# layout3.net
KiCad netlist of a schematic drawn in EAGLE
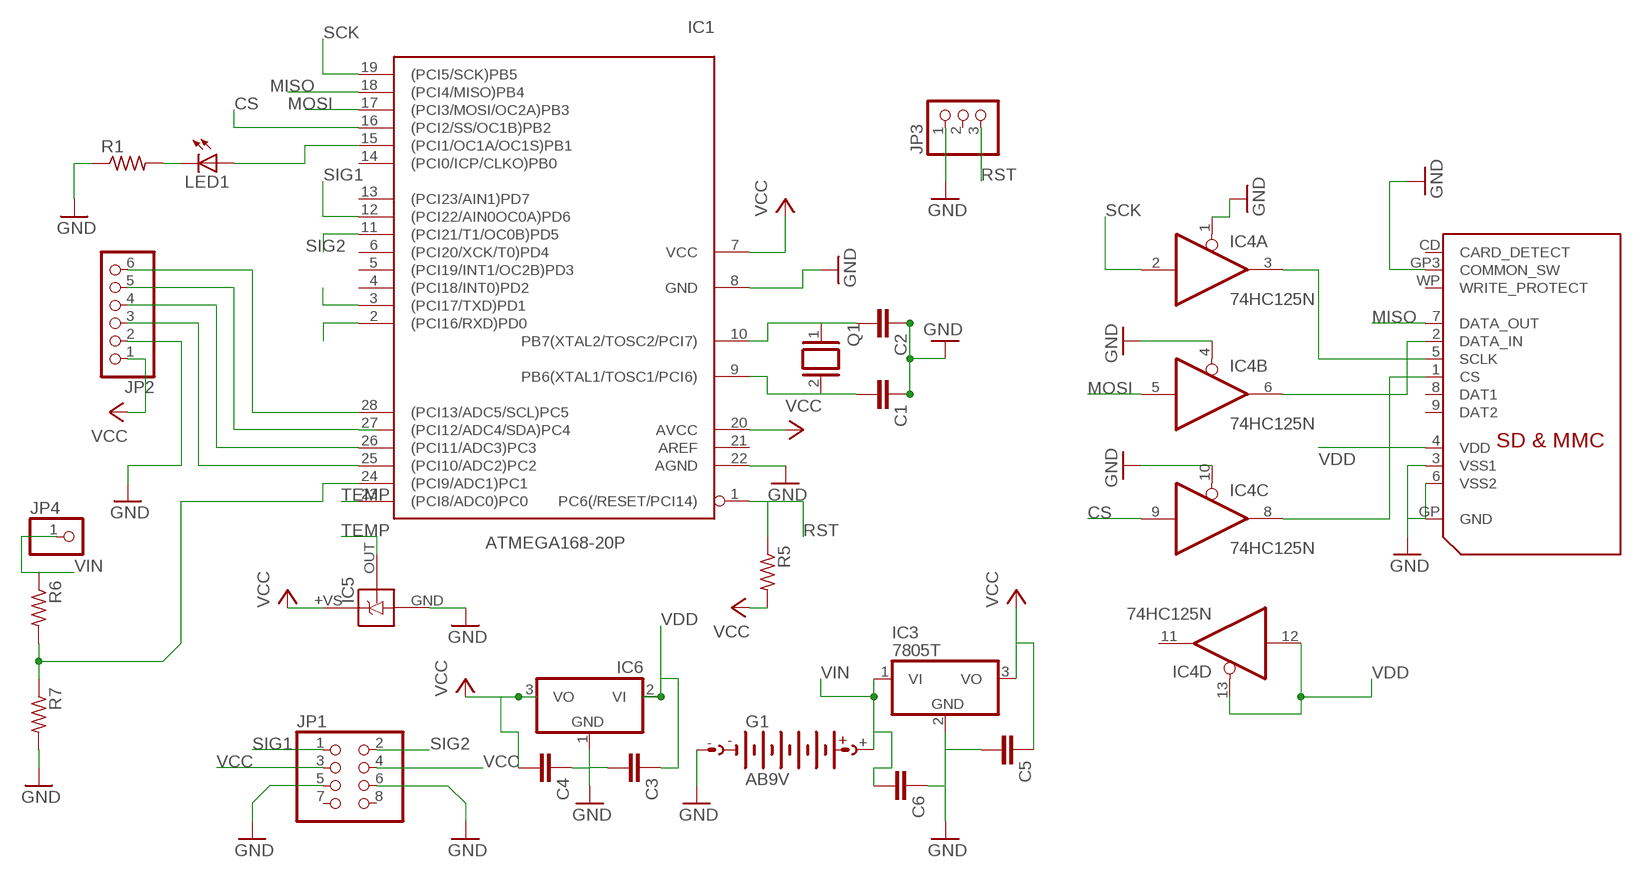
[diagram p0: schematic, sheet 1]

(export (version "E")
  (design (tool "Eeschema 10.0.6"))
  (components
    (comp (ref "C1")
      (value "C-EU025-025X050")
      (footprint "eagle-import:C025-025X050")
      (libsource (lib "eagle-import") (part "C-EU025-025X050"))
    )
    (comp (ref "C2")
      (value "C-EU025-025X050")
      (footprint "eagle-import:C025-025X050")
      (libsource (lib "eagle-import") (part "C-EU025-025X050"))
    )
    (comp (ref "C3")
      (value "C-EU025-025X050")
      (footprint "eagle-import:C025-025X050")
      (libsource (lib "eagle-import") (part "C-EU025-025X050"))
    )
    (comp (ref "C4")
      (value "C-EU025-025X050")
      (footprint "eagle-import:C025-025X050")
      (libsource (lib "eagle-import") (part "C-EU025-025X050"))
    )
    (comp (ref "C5")
      (value "C-EU025-025X050")
      (footprint "eagle-import:C025-025X050")
      (libsource (lib "eagle-import") (part "C-EU025-025X050"))
    )
    (comp (ref "C6")
      (value "C-EU025-025X050")
      (footprint "eagle-import:C025-025X050")
      (libsource (lib "eagle-import") (part "C-EU025-025X050"))
    )
    (comp (ref "G1")
      (value "AB9V")
      (footprint "eagle-import:AB9V")
      (libsource (lib "eagle-import") (part "AB9V"))
    )
    (comp (ref "IC1")
      (value "ATMEGA168-20P")
      (footprint "eagle-import:DIL28-3")
      (libsource (lib "eagle-import") (part "ATMEGA168P-20"))
    )
    (comp (ref "IC3")
      (value "7805T")
      (footprint "eagle-import:TO220H")
      (libsource (lib "eagle-import") (part "78T05"))
    )
    (comp (ref "IC4")
      (value "74HC125N")
      (footprint "eagle-import:DIL14")
      (libsource (lib "eagle-import") (part "74125NHC"))
    )
    (comp (ref "IC5")
      (value "LM35")
      (footprint "eagle-import:TO-92-")
      (libsource (lib "eagle-import") (part "LM35"))
    )
    (comp (ref "IC6")
      (value "7906T")
      (footprint "eagle-import:TO220H")
      (libsource (lib "eagle-import") (part "79T06"))
    )
    (comp (ref "JP1")
      (value "PINHD-2X4")
      (footprint "eagle-import:2X04")
      (libsource (lib "eagle-import") (part "PINHD-2X4"))
    )
    (comp (ref "JP2")
      (value "PINHD-1X6CB")
      (footprint "eagle-import:1X06-CLEANBIG")
      (libsource (lib "eagle-import") (part "PINHD-1X6CB"))
    )
    (comp (ref "JP3")
      (value "PINHD-1X3CB")
      (footprint "eagle-import:1X03-CLEANBIG")
      (libsource (lib "eagle-import") (part "PINHD-1X3CB"))
    )
    (comp (ref "JP4")
      (value "PINHD-1X1CB")
      (footprint "eagle-import:1X01-CLEANBIG")
      (libsource (lib "eagle-import") (part "PINHD-1X1CB"))
    )
    (comp (ref "LED1")
      (value "LED5MM")
      (footprint "eagle-import:LED5MM")
      (libsource (lib "eagle-import") (part "LED5MM"))
    )
    (comp (ref "Q1")
      (value "XTAL/S")
      (footprint "eagle-import:QS")
      (libsource (lib "eagle-import") (part "XTAL/S"))
    )
    (comp (ref "R1")
      (value "R-US_0207/10")
      (footprint "eagle-import:0207_10")
      (libsource (lib "eagle-import") (part "R-US_0207/10"))
    )
    (comp (ref "R5")
      (value "R-US_0207/10")
      (footprint "eagle-import:0207_10")
      (libsource (lib "eagle-import") (part "R-US_0207/10"))
    )
    (comp (ref "R6")
      (value "R-US_0207/10")
      (footprint "eagle-import:0207_10")
      (libsource (lib "eagle-import") (part "R-US_0207/10"))
    )
    (comp (ref "R7")
      (value "R-US_0207/10")
      (footprint "eagle-import:0207_10")
      (libsource (lib "eagle-import") (part "R-US_0207/10"))
    )
    (comp (ref "U$1")
      (value "SDMMC06132")
      (footprint "eagle-import:06132")
      (libsource (lib "eagle-import") (part "SDMMC06132"))
    )
  )
  (nets
    (net (code "1") (name "/CS") (class "Default")
      (node (ref "IC1") (pin "16") (pinfunction "(PCI2/SS/OC1B)PB2_16") (pintype "bidirectional"))
      (node (ref "IC4") (pin "9") (pinfunction "I_9") (pintype "input"))
    )
    (net (code "2") (name "/MISO") (class "Default")
      (node (ref "IC1") (pin "18") (pinfunction "(PCI4/MISO)PB4_18") (pintype "bidirectional"))
      (node (ref "U$1") (pin "7") (pinfunction "DATA_OUT_7") (pintype "output"))
    )
    (net (code "3") (name "/MOSI") (class "Default")
      (node (ref "IC1") (pin "17") (pinfunction "(PCI3/MOSI/OC2A)PB3_17") (pintype "bidirectional"))
      (node (ref "IC4") (pin "5") (pinfunction "I_5") (pintype "input"))
    )
    (net (code "4") (name "/RST") (class "Default")
      (node (ref "IC1") (pin "1") (pinfunction "PC6(/RESET/PCI14)_1") (pintype "bidirectional"))
      (node (ref "JP3") (pin "3") (pinfunction "3_3") (pintype "passive"))
      (node (ref "R5") (pin "1") (pinfunction "1_1") (pintype "passive"))
    )
    (net (code "5") (name "/SCK") (class "Default")
      (node (ref "IC1") (pin "19") (pinfunction "(PCI5/SCK)PB5_19") (pintype "bidirectional"))
      (node (ref "IC4") (pin "2") (pinfunction "I_2") (pintype "input"))
    )
    (net (code "6") (name "/SIG1") (class "Default")
      (node (ref "IC1") (pin "12") (pinfunction "(PCI22/AIN0OC0A)PD6_12") (pintype "bidirectional"))
      (node (ref "JP1") (pin "1") (pinfunction "1_1") (pintype "passive"))
    )
    (net (code "7") (name "/SIG2") (class "Default")
      (node (ref "IC1") (pin "11") (pinfunction "(PCI21/T1/OC0B)PD5_11") (pintype "bidirectional"))
      (node (ref "JP1") (pin "2") (pinfunction "2_2") (pintype "passive"))
    )
    (net (code "8") (name "/TEMP") (class "Default")
      (node (ref "IC1") (pin "23") (pinfunction "(PCI8/ADC0)PC0_23") (pintype "bidirectional"))
      (node (ref "IC5") (pin "OUT") (pinfunction "OUT_OUT") (pintype "bidirectional"))
    )
    (net (code "9") (name "/VDD") (class "Default")
      (node (ref "C3") (pin "1") (pinfunction "1_1") (pintype "passive"))
      (node (ref "IC4") (pin "12") (pinfunction "I_12") (pintype "input"))
      (node (ref "IC4") (pin "13") (pinfunction "OE_13") (pintype "input"))
      (node (ref "IC6") (pin "2") (pinfunction "VI_2") (pintype "input"))
      (node (ref "U$1") (pin "4") (pinfunction "VDD_4") (pintype "power_in"))
    )
    (net (code "10") (name "/VIN") (class "Default")
      (node (ref "C6") (pin "2") (pinfunction "2_2") (pintype "passive"))
      (node (ref "G1") (pin "+") (pinfunction "+_+") (pintype "passive"))
      (node (ref "IC3") (pin "1") (pinfunction "VI_1") (pintype "input"))
      (node (ref "JP4") (pin "1") (pinfunction "1_1") (pintype "passive"))
      (node (ref "R6") (pin "1") (pinfunction "1_1") (pintype "passive"))
    )
    (net (code "11") (name "GND") (class "Default")
      (node (ref "C1") (pin "1") (pinfunction "1_1") (pintype "passive"))
      (node (ref "C2") (pin "1") (pinfunction "1_1") (pintype "passive"))
      (node (ref "C3") (pin "2") (pinfunction "2_2") (pintype "passive"))
      (node (ref "C4") (pin "1") (pinfunction "1_1") (pintype "passive"))
      (node (ref "C5") (pin "2") (pinfunction "2_2") (pintype "passive"))
      (node (ref "C6") (pin "1") (pinfunction "1_1") (pintype "passive"))
      (node (ref "G1") (pin "-") (pinfunction "-_-") (pintype "passive"))
      (node (ref "IC1") (pin "22") (pinfunction "AGND_22") (pintype "bidirectional"))
      (node (ref "IC1") (pin "8") (pinfunction "GND_8") (pintype "bidirectional"))
      (node (ref "IC3") (pin "2") (pinfunction "GND_2") (pintype "passive"))
      (node (ref "IC4") (pin "1") (pinfunction "OE_1") (pintype "input"))
      (node (ref "IC4") (pin "10") (pinfunction "OE_10") (pintype "input"))
      (node (ref "IC4") (pin "4") (pinfunction "OE_4") (pintype "input"))
      (node (ref "IC5") (pin "GND") (pinfunction "GND_GND") (pintype "bidirectional"))
      (node (ref "IC6") (pin "1") (pinfunction "GND_1") (pintype "passive"))
      (node (ref "JP1") (pin "5") (pinfunction "5_5") (pintype "passive"))
      (node (ref "JP1") (pin "6") (pinfunction "6_6") (pintype "passive"))
      (node (ref "JP2") (pin "2") (pinfunction "2_2") (pintype "passive"))
      (node (ref "JP3") (pin "1") (pinfunction "1_1") (pintype "passive"))
      (node (ref "R1") (pin "1") (pinfunction "1_1") (pintype "passive"))
      (node (ref "R7") (pin "2") (pinfunction "2_2") (pintype "passive"))
      (node (ref "U$1") (pin "3") (pinfunction "VSS1_3") (pintype "power_in"))
      (node (ref "U$1") (pin "6") (pinfunction "VSS2_6") (pintype "power_in"))
      (node (ref "U$1") (pin "GP") (pinfunction "GND_GP") (pintype "power_in"))
      (node (ref "U$1") (pin "GP3") (pinfunction "COMMON_SW_GP3") (pintype "passive"))
    )
    (net (code "12") (name "Net-(IC1-(PCI1{slash}OC1A{slash}OC1S)PB1)") (class "Default")
      (node (ref "IC1") (pin "15") (pinfunction "(PCI1/OC1A/OC1S)PB1_15") (pintype "bidirectional"))
      (node (ref "LED1") (pin "A") (pinfunction "A_A") (pintype "passive"))
    )
    (net (code "13") (name "Net-(IC1-(PCI9{slash}ADC1)PC1)") (class "Default")
      (node (ref "IC1") (pin "24") (pinfunction "(PCI9/ADC1)PC1_24") (pintype "bidirectional"))
      (node (ref "R6") (pin "2") (pinfunction "2_2") (pintype "passive"))
      (node (ref "R7") (pin "1") (pinfunction "1_1") (pintype "passive"))
    )
    (net (code "14") (name "Net-(IC1-(PCI10{slash}ADC2)PC2)") (class "Default")
      (node (ref "IC1") (pin "25") (pinfunction "(PCI10/ADC2)PC2_25") (pintype "bidirectional"))
      (node (ref "JP2") (pin "3") (pinfunction "3_3") (pintype "passive"))
    )
    (net (code "15") (name "Net-(IC1-(PCI11{slash}ADC3)PC3)") (class "Default")
      (node (ref "IC1") (pin "26") (pinfunction "(PCI11/ADC3)PC3_26") (pintype "bidirectional"))
      (node (ref "JP2") (pin "4") (pinfunction "4_4") (pintype "passive"))
    )
    (net (code "16") (name "Net-(IC1-(PCI12{slash}ADC4{slash}SDA)PC4)") (class "Default")
      (node (ref "IC1") (pin "27") (pinfunction "(PCI12/ADC4/SDA)PC4_27") (pintype "bidirectional"))
      (node (ref "JP2") (pin "5") (pinfunction "5_5") (pintype "passive"))
    )
    (net (code "17") (name "Net-(IC1-(PCI13{slash}ADC5{slash}SCL)PC5)") (class "Default")
      (node (ref "IC1") (pin "28") (pinfunction "(PCI13/ADC5/SCL)PC5_28") (pintype "bidirectional"))
      (node (ref "JP2") (pin "6") (pinfunction "6_6") (pintype "passive"))
    )
    (net (code "18") (name "Net-(IC1-PB6(XTAL1{slash}TOSC1{slash}PCI6))") (class "Default")
      (node (ref "C1") (pin "2") (pinfunction "2_2") (pintype "passive"))
      (node (ref "IC1") (pin "9") (pinfunction "PB6(XTAL1/TOSC1/PCI6)_9") (pintype "bidirectional"))
      (node (ref "Q1") (pin "2") (pinfunction "2_2") (pintype "passive"))
    )
    (net (code "19") (name "Net-(IC1-PB7(XTAL2{slash}TOSC2{slash}PCI7))") (class "Default")
      (node (ref "C2") (pin "2") (pinfunction "2_2") (pintype "passive"))
      (node (ref "IC1") (pin "10") (pinfunction "PB7(XTAL2/TOSC2/PCI7)_10") (pintype "bidirectional"))
      (node (ref "Q1") (pin "1") (pinfunction "1_1") (pintype "passive"))
    )
    (net (code "20") (name "Net-(IC4A-O)") (class "Default")
      (node (ref "IC4") (pin "3") (pinfunction "O_3") (pintype "tri_state"))
      (node (ref "U$1") (pin "5") (pinfunction "SCLK_5") (pintype "input"))
    )
    (net (code "21") (name "Net-(IC4B-O)") (class "Default")
      (node (ref "IC4") (pin "6") (pinfunction "O_6") (pintype "tri_state"))
      (node (ref "U$1") (pin "2") (pinfunction "DATA_IN_2") (pintype "input"))
    )
    (net (code "22") (name "Net-(IC4C-O)") (class "Default")
      (node (ref "IC4") (pin "8") (pinfunction "O_8") (pintype "tri_state"))
      (node (ref "U$1") (pin "1") (pinfunction "CS_1") (pintype "input"))
    )
    (net (code "23") (name "Net-(LED1-C)") (class "Default")
      (node (ref "LED1") (pin "K") (pinfunction "C_K") (pintype "passive"))
      (node (ref "R1") (pin "2") (pinfunction "2_2") (pintype "passive"))
    )
    (net (code "24") (name "VCC") (class "Default")
      (node (ref "C4") (pin "2") (pinfunction "2_2") (pintype "passive"))
      (node (ref "C5") (pin "1") (pinfunction "1_1") (pintype "passive"))
      (node (ref "IC1") (pin "20") (pinfunction "AVCC_20") (pintype "bidirectional"))
      (node (ref "IC1") (pin "7") (pinfunction "VCC_7") (pintype "bidirectional"))
      (node (ref "IC3") (pin "3") (pinfunction "VO_3") (pintype "passive"))
      (node (ref "IC5") (pin "+VS") (pinfunction "+VS_+VS") (pintype "bidirectional"))
      (node (ref "IC6") (pin "3") (pinfunction "VO_3") (pintype "passive"))
      (node (ref "JP1") (pin "3") (pinfunction "3_3") (pintype "passive"))
      (node (ref "JP1") (pin "4") (pinfunction "4_4") (pintype "passive"))
      (node (ref "JP2") (pin "1") (pinfunction "1_1") (pintype "passive"))
      (node (ref "R5") (pin "2") (pinfunction "2_2") (pintype "passive"))
    )
    (net (code "25") (name "unconnected-(IC1-(PCI0{slash}ICP{slash}CLKO)PB0-Pad14)") (class "Default")
      (node (ref "IC1") (pin "14") (pinfunction "(PCI0/ICP/CLKO)PB0_14") (pintype "bidirectional"))
    )
    (net (code "26") (name "unconnected-(IC1-(PCI16{slash}RXD)PD0-Pad2)") (class "Default")
      (node (ref "IC1") (pin "2") (pinfunction "(PCI16/RXD)PD0_2") (pintype "bidirectional"))
    )
    (net (code "27") (name "unconnected-(IC1-(PCI17{slash}TXD)PD1-Pad3)") (class "Default")
      (node (ref "IC1") (pin "3") (pinfunction "(PCI17/TXD)PD1_3") (pintype "bidirectional"))
    )
    (net (code "28") (name "unconnected-(IC1-(PCI18{slash}INT0)PD2-Pad4)") (class "Default")
      (node (ref "IC1") (pin "4") (pinfunction "(PCI18/INT0)PD2_4") (pintype "bidirectional"))
    )
    (net (code "29") (name "unconnected-(IC1-(PCI19{slash}INT1{slash}OC2B)PD3-Pad5)") (class "Default")
      (node (ref "IC1") (pin "5") (pinfunction "(PCI19/INT1/OC2B)PD3_5") (pintype "bidirectional"))
    )
    (net (code "30") (name "unconnected-(IC1-(PCI20{slash}XCK{slash}T0)PD4-Pad6)") (class "Default")
      (node (ref "IC1") (pin "6") (pinfunction "(PCI20/XCK/T0)PD4_6") (pintype "bidirectional"))
    )
    (net (code "31") (name "unconnected-(IC1-(PCI23{slash}AIN1)PD7-Pad13)") (class "Default")
      (node (ref "IC1") (pin "13") (pinfunction "(PCI23/AIN1)PD7_13") (pintype "bidirectional"))
    )
    (net (code "32") (name "unconnected-(IC1-AREF-Pad21)") (class "Default")
      (node (ref "IC1") (pin "21") (pinfunction "AREF_21") (pintype "bidirectional"))
    )
    (net (code "33") (name "unconnected-(IC4D-O-Pad11)") (class "Default")
      (node (ref "IC4") (pin "11") (pinfunction "O_11") (pintype "tri_state"))
    )
    (net (code "34") (name "unconnected-(JP1-Pad7)") (class "Default")
      (node (ref "JP1") (pin "7") (pinfunction "7_7") (pintype "passive"))
    )
    (net (code "35") (name "unconnected-(JP1-Pad8)") (class "Default")
      (node (ref "JP1") (pin "8") (pinfunction "8_8") (pintype "passive"))
    )
    (net (code "36") (name "unconnected-(JP3-Pad2)") (class "Default")
      (node (ref "JP3") (pin "2") (pinfunction "2_2") (pintype "passive"))
    )
    (net (code "37") (name "unconnected-(U$1-CARD_DETECT-PadCD)") (class "Default")
      (node (ref "U$1") (pin "CD") (pinfunction "CARD_DETECT_CD") (pintype "passive"))
    )
    (net (code "38") (name "unconnected-(U$1-DAT1-Pad8)") (class "Default")
      (node (ref "U$1") (pin "8") (pinfunction "DAT1_8") (pintype "bidirectional"))
    )
    (net (code "39") (name "unconnected-(U$1-DAT2-Pad9)") (class "Default")
      (node (ref "U$1") (pin "9") (pinfunction "DAT2_9") (pintype "bidirectional"))
    )
    (net (code "40") (name "unconnected-(U$1-WRITE_PROTECT-PadWP)") (class "Default")
      (node (ref "U$1") (pin "WP") (pinfunction "WRITE_PROTECT_WP") (pintype "passive"))
    )
  )
)
